# FPGA.net
KiCad netlist of a schematic drawn in Altium Designer
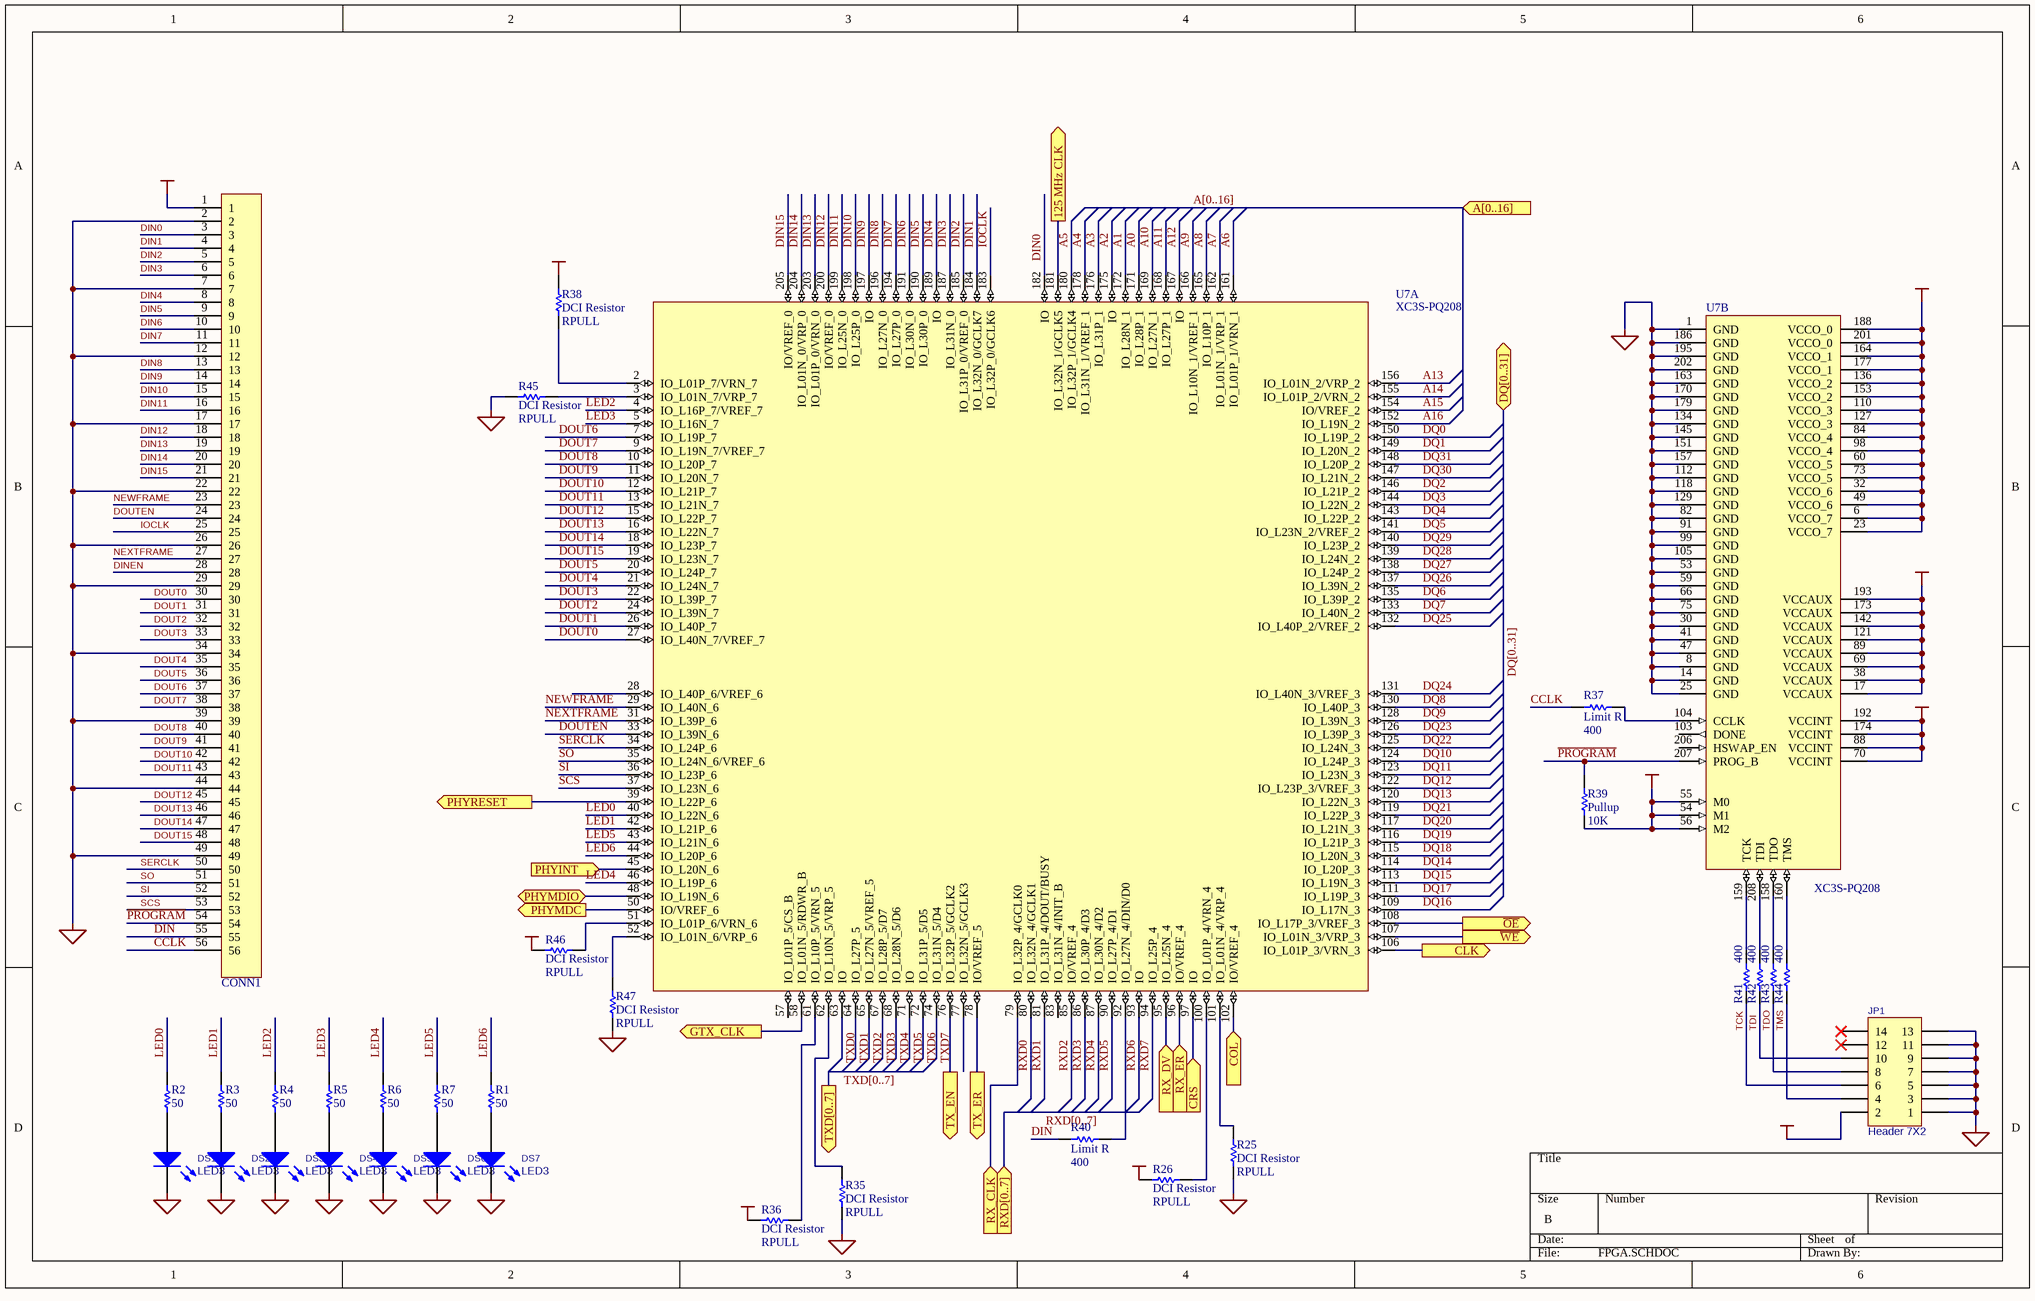
[diagram p0: FPGA.SCHDOC]

(export (version "E")
  (design (tool "Eeschema 10.0.6"))
  (components
    (comp (ref "CONN1") (value "CON56B") (footprint "HDR56F") (libsource (lib "parts") (part "CON56B")))
    (comp (ref "DS1")
      (value "LED3")
      (footprint "SMD _LED")
      (description "Typical BLUE SiC LED")
      (fields (field (name "PUBLISHER") "Altium Limited"))
      (libsource (lib "Miscellaneous Devices") (part "LED3"))
    )
    (comp (ref "DS2")
      (value "LED3")
      (footprint "SMD _LED")
      (description "Typical BLUE SiC LED")
      (fields (field (name "PUBLISHER") "Altium Limited"))
      (libsource (lib "Miscellaneous Devices") (part "LED3"))
    )
    (comp (ref "DS3")
      (value "LED3")
      (footprint "SMD _LED")
      (description "Typical BLUE SiC LED")
      (fields (field (name "PUBLISHER") "Altium Limited"))
      (libsource (lib "Miscellaneous Devices") (part "LED3"))
    )
    (comp (ref "DS4")
      (value "LED3")
      (footprint "SMD _LED")
      (description "Typical BLUE SiC LED")
      (fields (field (name "PUBLISHER") "Altium Limited"))
      (libsource (lib "Miscellaneous Devices") (part "LED3"))
    )
    (comp (ref "DS5")
      (value "LED3")
      (footprint "SMD _LED")
      (description "Typical BLUE SiC LED")
      (fields (field (name "PUBLISHER") "Altium Limited"))
      (libsource (lib "Miscellaneous Devices") (part "LED3"))
    )
    (comp (ref "DS6")
      (value "LED3")
      (footprint "SMD _LED")
      (description "Typical BLUE SiC LED")
      (fields (field (name "PUBLISHER") "Altium Limited"))
      (libsource (lib "Miscellaneous Devices") (part "LED3"))
    )
    (comp (ref "DS7")
      (value "LED3")
      (footprint "SMD _LED")
      (description "Typical BLUE SiC LED")
      (fields (field (name "PUBLISHER") "Altium Limited"))
      (libsource (lib "Miscellaneous Devices") (part "LED3"))
    )
    (comp (ref "JP1")
      (value "Header 7X2")
      (footprint "SMT 2x7 2mm HDR")
      (description "Header, 7-Pin, Dual row")
      (fields (field (name "MANUFACTURER") "Generic Components") (field (name "PUBLISHER") "Altium Limited"))
      (libsource (lib "Miscellaneous Connectors") (part "Header 7X2"))
    )
    (comp (ref "R1")
      (value "50")
      (footprint "0603")
      (description "Standard Passive Resistor")
      (fields (field (name "TOLERANCE") "1%") (field (name "Comment") "RESISTOR"))
      (libsource (lib "parts") (part "RESISTOR"))
    )
    (comp (ref "R2")
      (value "50")
      (footprint "0603")
      (description "Standard Passive Resistor")
      (fields (field (name "TOLERANCE") "1%") (field (name "Comment") "RESISTOR"))
      (libsource (lib "parts") (part "RESISTOR"))
    )
    (comp (ref "R3")
      (value "50")
      (footprint "0603")
      (description "Standard Passive Resistor")
      (fields (field (name "TOLERANCE") "1%") (field (name "Comment") "RESISTOR"))
      (libsource (lib "parts") (part "RESISTOR"))
    )
    (comp (ref "R4")
      (value "50")
      (footprint "0603")
      (description "Standard Passive Resistor")
      (fields (field (name "TOLERANCE") "1%") (field (name "Comment") "RESISTOR"))
      (libsource (lib "parts") (part "RESISTOR"))
    )
    (comp (ref "R5")
      (value "50")
      (footprint "0603")
      (description "Standard Passive Resistor")
      (fields (field (name "TOLERANCE") "1%") (field (name "Comment") "RESISTOR"))
      (libsource (lib "parts") (part "RESISTOR"))
    )
    (comp (ref "R6")
      (value "50")
      (footprint "0603")
      (description "Standard Passive Resistor")
      (fields (field (name "TOLERANCE") "1%") (field (name "Comment") "RESISTOR"))
      (libsource (lib "parts") (part "RESISTOR"))
    )
    (comp (ref "R7")
      (value "50")
      (footprint "0603")
      (description "Standard Passive Resistor")
      (fields (field (name "TOLERANCE") "1%") (field (name "Comment") "RESISTOR"))
      (libsource (lib "parts") (part "RESISTOR"))
    )
    (comp (ref "R25")
      (value "DCI Resistor")
      (footprint "0603")
      (description "Resistor")
      (fields
        (field (name "MANUFACTURER") "Generic Components")
        (field (name "ALTIUM_VALUE") "RPULL")
        (field (name "PUBLISHER") "Altium Limited")
      )
      (libsource (lib "Miscellaneous Devices") (part "Res1"))
    )
    (comp (ref "R26")
      (value "DCI Resistor")
      (footprint "0603")
      (description "Resistor")
      (fields
        (field (name "MANUFACTURER") "Generic Components")
        (field (name "ALTIUM_VALUE") "RPULL")
        (field (name "PUBLISHER") "Altium Limited")
      )
      (libsource (lib "Miscellaneous Devices") (part "Res1"))
    )
    (comp (ref "R35")
      (value "DCI Resistor")
      (footprint "0603")
      (description "Resistor")
      (fields
        (field (name "MANUFACTURER") "Generic Components")
        (field (name "ALTIUM_VALUE") "RPULL")
        (field (name "PUBLISHER") "Altium Limited")
      )
      (libsource (lib "Miscellaneous Devices") (part "Res1"))
    )
    (comp (ref "R36")
      (value "DCI Resistor")
      (footprint "0603")
      (description "Resistor")
      (fields
        (field (name "MANUFACTURER") "Generic Components")
        (field (name "ALTIUM_VALUE") "RPULL")
        (field (name "PUBLISHER") "Altium Limited")
      )
      (libsource (lib "Miscellaneous Devices") (part "Res1"))
    )
    (comp (ref "R37")
      (value "Limit R")
      (footprint "0603")
      (description "Standard Passive Resistor")
      (fields (field (name "ALTIUM_VALUE") "400") (field (name "TOLERANCE") "1%"))
      (libsource (lib "parts") (part "RESISTOR"))
    )
    (comp (ref "R38")
      (value "DCI Resistor")
      (footprint "0603")
      (description "Resistor")
      (fields
        (field (name "MANUFACTURER") "Generic Components")
        (field (name "ALTIUM_VALUE") "RPULL")
        (field (name "PUBLISHER") "Altium Limited")
      )
      (libsource (lib "Miscellaneous Devices") (part "Res1"))
    )
    (comp (ref "R39")
      (value "Pullup")
      (footprint "0603")
      (description "Resistor")
      (fields
        (field (name "MANUFACTURER") "Generic Components")
        (field (name "ALTIUM_VALUE") "10K")
        (field (name "PUBLISHER") "Altium Limited")
      )
      (libsource (lib "Miscellaneous Devices") (part "Res1"))
    )
    (comp (ref "R40")
      (value "Limit R")
      (footprint "0603")
      (description "Standard Passive Resistor")
      (fields (field (name "ALTIUM_VALUE") "400") (field (name "TOLERANCE") "1%"))
      (libsource (lib "parts") (part "RESISTOR"))
    )
    (comp (ref "R41")
      (value "400")
      (footprint "0603")
      (description "Standard Passive Resistor")
      (fields (field (name "TOLERANCE") "1%") (field (name "Comment") "RESISTOR"))
      (libsource (lib "parts") (part "RESISTOR"))
    )
    (comp (ref "R42")
      (value "400")
      (footprint "0603")
      (description "Standard Passive Resistor")
      (fields (field (name "TOLERANCE") "1%") (field (name "Comment") "RESISTOR"))
      (libsource (lib "parts") (part "RESISTOR"))
    )
    (comp (ref "R43")
      (value "400")
      (footprint "0603")
      (description "Standard Passive Resistor")
      (fields (field (name "TOLERANCE") "1%") (field (name "Comment") "RESISTOR"))
      (libsource (lib "parts") (part "RESISTOR"))
    )
    (comp (ref "R44")
      (value "400")
      (footprint "0603")
      (description "Standard Passive Resistor")
      (fields (field (name "TOLERANCE") "1%") (field (name "Comment") "RESISTOR"))
      (libsource (lib "parts") (part "RESISTOR"))
    )
    (comp (ref "R45")
      (value "DCI Resistor")
      (footprint "0603")
      (description "Resistor")
      (fields
        (field (name "MANUFACTURER") "Generic Components")
        (field (name "ALTIUM_VALUE") "RPULL")
        (field (name "PUBLISHER") "Altium Limited")
      )
      (libsource (lib "Miscellaneous Devices") (part "Res1"))
    )
    (comp (ref "R46")
      (value "DCI Resistor")
      (footprint "0603")
      (description "Resistor")
      (fields
        (field (name "MANUFACTURER") "Generic Components")
        (field (name "ALTIUM_VALUE") "RPULL")
        (field (name "PUBLISHER") "Altium Limited")
      )
      (libsource (lib "Miscellaneous Devices") (part "Res1"))
    )
    (comp (ref "R47")
      (value "DCI Resistor")
      (footprint "0603")
      (description "Resistor")
      (fields
        (field (name "MANUFACTURER") "Generic Components")
        (field (name "ALTIUM_VALUE") "RPULL")
        (field (name "PUBLISHER") "Altium Limited")
      )
      (libsource (lib "Miscellaneous Devices") (part "Res1"))
    )
    (comp (ref "U7")
      (value "XC3S-PQ208")
      (footprint "F-QFP28X28-G208/Z32N")
      (description "Xilinx Spartan-3 PQ208")
      (libsource (lib "My devices") (part "XC3S-PQ208"))
    )
  )
  (nets
    (net (code "1") (name "+1.2VCC") (class "Default")
      (node (ref "U7") (pin "174") (pinfunction "VCCINT_174") (pintype "power_in"))
      (node (ref "U7") (pin "192") (pinfunction "VCCINT_192") (pintype "power_in"))
      (node (ref "U7") (pin "70") (pinfunction "VCCINT_70") (pintype "power_in"))
      (node (ref "U7") (pin "88") (pinfunction "VCCINT_88") (pintype "power_in"))
    )
    (net (code "2") (name "+2.5VCC") (class "Default")
      (node (ref "U7") (pin "121") (pinfunction "VCCAUX_121") (pintype "power_in"))
      (node (ref "U7") (pin "142") (pinfunction "VCCAUX_142") (pintype "power_in"))
      (node (ref "U7") (pin "17") (pinfunction "VCCAUX_17") (pintype "power_in"))
      (node (ref "U7") (pin "173") (pinfunction "VCCAUX_173") (pintype "power_in"))
      (node (ref "U7") (pin "193") (pinfunction "VCCAUX_193") (pintype "power_in"))
      (node (ref "U7") (pin "38") (pinfunction "VCCAUX_38") (pintype "power_in"))
      (node (ref "U7") (pin "69") (pinfunction "VCCAUX_69") (pintype "power_in"))
      (node (ref "U7") (pin "89") (pinfunction "VCCAUX_89") (pintype "power_in"))
    )
    (net (code "3") (name "/125 MHz CLK") (class "Default")
      (node (ref "U7") (pin "181") (pinfunction "IO_L32N_1/GCLK5_181") (pintype "bidirectional"))
    )
    (net (code "4") (name "/A0") (class "Default")
      (node (ref "U7") (pin "171") (pinfunction "IO_L28P_1_171") (pintype "bidirectional"))
    )
    (net (code "5") (name "/A1") (class "Default")
      (node (ref "U7") (pin "172") (pinfunction "IO_L28N_1_172") (pintype "bidirectional"))
    )
    (net (code "6") (name "/A2") (class "Default")
      (node (ref "U7") (pin "175") (pinfunction "IO_175") (pintype "bidirectional"))
    )
    (net (code "7") (name "/A3") (class "Default")
      (node (ref "U7") (pin "176") (pinfunction "IO_L31P_1_176") (pintype "bidirectional"))
    )
    (net (code "8") (name "/A4") (class "Default")
      (node (ref "U7") (pin "178") (pinfunction "IO_L31N_1/VREF_1_178") (pintype "bidirectional"))
    )
    (net (code "9") (name "/A5") (class "Default")
      (node (ref "U7") (pin "180") (pinfunction "IO_L32P_1/GCLK4_180") (pintype "bidirectional"))
    )
    (net (code "10") (name "/A6") (class "Default")
      (node (ref "U7") (pin "161") (pinfunction "IO_L01P_1/VRN_1_161") (pintype "bidirectional"))
    )
    (net (code "11") (name "/A7") (class "Default")
      (node (ref "U7") (pin "162") (pinfunction "IO_L01N_1/VRP_1_162") (pintype "bidirectional"))
    )
    (net (code "12") (name "/A8") (class "Default")
      (node (ref "U7") (pin "165") (pinfunction "IO_L10P_1_165") (pintype "bidirectional"))
    )
    (net (code "13") (name "/A9") (class "Default")
      (node (ref "U7") (pin "166") (pinfunction "IO_L10N_1/VREF_1_166") (pintype "bidirectional"))
    )
    (net (code "14") (name "/A10") (class "Default")
      (node (ref "U7") (pin "169") (pinfunction "IO_L27N_1_169") (pintype "bidirectional"))
    )
    (net (code "15") (name "/A11") (class "Default")
      (node (ref "U7") (pin "168") (pinfunction "IO_L27P_1_168") (pintype "bidirectional"))
    )
    (net (code "16") (name "/A12") (class "Default")
      (node (ref "U7") (pin "167") (pinfunction "IO_167") (pintype "bidirectional"))
    )
    (net (code "17") (name "/A13") (class "Default")
      (node (ref "U7") (pin "156") (pinfunction "IO_L01N_2/VRP_2_156") (pintype "bidirectional"))
    )
    (net (code "18") (name "/A14") (class "Default")
      (node (ref "U7") (pin "155") (pinfunction "IO_L01P_2/VRN_2_155") (pintype "bidirectional"))
    )
    (net (code "19") (name "/A15") (class "Default")
      (node (ref "U7") (pin "154") (pinfunction "IO/VREF_2_154") (pintype "bidirectional"))
    )
    (net (code "20") (name "/A16") (class "Default")
      (node (ref "U7") (pin "152") (pinfunction "IO_L19N_2_152") (pintype "bidirectional"))
    )
    (net (code "22") (name "/CCLK") (class "Default")
      (node (ref "CONN1") (pin "56") (pinfunction "56_56") (pintype "passive"))
      (node (ref "R37") (pin "2") (pintype "passive"))
    )
    (net (code "23") (name "/CLK") (class "Default")
      (node (ref "U7") (pin "106") (pinfunction "IO_L01P_3/VRN_3_106") (pintype "bidirectional"))
    )
    (net (code "24") (name "/COL") (class "Default")
      (node (ref "U7") (pin "102") (pinfunction "IO/VREF_4_102") (pintype "bidirectional"))
    )
    (net (code "25") (name "/CRS") (class "Default")
      (node (ref "U7") (pin "97") (pinfunction "IO_97") (pintype "bidirectional"))
    )
    (net (code "26") (name "/DIN") (class "Default")
      (node (ref "CONN1") (pin "55") (pinfunction "55_55") (pintype "passive"))
      (node (ref "R40") (pin "2") (pintype "passive"))
    )
    (net (code "27") (name "/DIN0") (class "Default")
      (node (ref "CONN1") (pin "3") (pinfunction "3_3") (pintype "passive"))
      (node (ref "U7") (pin "182") (pinfunction "IO_182") (pintype "bidirectional"))
    )
    (net (code "28") (name "/DIN1") (class "Default")
      (node (ref "CONN1") (pin "4") (pinfunction "4_4") (pintype "passive"))
      (node (ref "U7") (pin "184") (pinfunction "IO_L32N_0/GCLK7_184") (pintype "bidirectional"))
    )
    (net (code "29") (name "/DIN2") (class "Default")
      (node (ref "CONN1") (pin "5") (pinfunction "5_5") (pintype "passive"))
      (node (ref "U7") (pin "185") (pinfunction "IO_L31P_0/VREF_0_185") (pintype "bidirectional"))
    )
    (net (code "30") (name "/DIN3") (class "Default")
      (node (ref "CONN1") (pin "6") (pinfunction "6_6") (pintype "passive"))
      (node (ref "U7") (pin "187") (pinfunction "IO_L31N_0_187") (pintype "bidirectional"))
    )
    (net (code "31") (name "/DIN4") (class "Default")
      (node (ref "CONN1") (pin "8") (pinfunction "8_8") (pintype "passive"))
      (node (ref "U7") (pin "189") (pinfunction "IO_189") (pintype "bidirectional"))
    )
    (net (code "32") (name "/DIN5") (class "Default")
      (node (ref "CONN1") (pin "9") (pinfunction "9_9") (pintype "passive"))
      (node (ref "U7") (pin "190") (pinfunction "IO_L30P_0_190") (pintype "bidirectional"))
    )
    (net (code "33") (name "/DIN6") (class "Default")
      (node (ref "CONN1") (pin "10") (pinfunction "10_10") (pintype "passive"))
      (node (ref "U7") (pin "191") (pinfunction "IO_L30N_0_191") (pintype "bidirectional"))
    )
    (net (code "34") (name "/DIN7") (class "Default")
      (node (ref "CONN1") (pin "11") (pinfunction "11_11") (pintype "passive"))
      (node (ref "U7") (pin "194") (pinfunction "IO_L27P_0_194") (pintype "bidirectional"))
    )
    (net (code "35") (name "/DIN8") (class "Default")
      (node (ref "CONN1") (pin "13") (pinfunction "13_13") (pintype "passive"))
      (node (ref "U7") (pin "196") (pinfunction "IO_L27N_0_196") (pintype "bidirectional"))
    )
    (net (code "36") (name "/DIN9") (class "Default")
      (node (ref "CONN1") (pin "14") (pinfunction "14_14") (pintype "passive"))
      (node (ref "U7") (pin "197") (pinfunction "IO_197") (pintype "bidirectional"))
    )
    (net (code "37") (name "/DIN10") (class "Default")
      (node (ref "CONN1") (pin "15") (pinfunction "15_15") (pintype "passive"))
      (node (ref "U7") (pin "198") (pinfunction "IO_L25P_0_198") (pintype "bidirectional"))
    )
    (net (code "38") (name "/DIN11") (class "Default")
      (node (ref "CONN1") (pin "16") (pinfunction "16_16") (pintype "passive"))
      (node (ref "U7") (pin "199") (pinfunction "IO_L25N_0_199") (pintype "bidirectional"))
    )
    (net (code "39") (name "/DIN12") (class "Default")
      (node (ref "CONN1") (pin "18") (pinfunction "18_18") (pintype "passive"))
      (node (ref "U7") (pin "200") (pinfunction "IO/VREF_0_200") (pintype "bidirectional"))
    )
    (net (code "40") (name "/DIN13") (class "Default")
      (node (ref "CONN1") (pin "19") (pinfunction "19_19") (pintype "passive"))
      (node (ref "U7") (pin "203") (pinfunction "IO_L01P_0/VRN_0_203") (pintype "bidirectional"))
    )
    (net (code "41") (name "/DIN14") (class "Default")
      (node (ref "CONN1") (pin "20") (pinfunction "20_20") (pintype "passive"))
      (node (ref "U7") (pin "204") (pinfunction "IO_L01N_0/VRP_0_204") (pintype "bidirectional"))
    )
    (net (code "42") (name "/DIN15") (class "Default")
      (node (ref "CONN1") (pin "21") (pinfunction "21_21") (pintype "passive"))
      (node (ref "U7") (pin "205") (pinfunction "IO/VREF_0_205") (pintype "bidirectional"))
    )
    (net (code "43") (name "/DINEN") (class "Default")
      (node (ref "CONN1") (pin "28") (pinfunction "28_28") (pintype "passive"))
    )
    (net (code "44") (name "/DOUT0") (class "Default")
      (node (ref "CONN1") (pin "30") (pinfunction "30_30") (pintype "passive"))
      (node (ref "U7") (pin "27") (pinfunction "IO_L40N_7/VREF_7_27") (pintype "bidirectional"))
    )
    (net (code "45") (name "/DOUT1") (class "Default")
      (node (ref "CONN1") (pin "31") (pinfunction "31_31") (pintype "passive"))
      (node (ref "U7") (pin "26") (pinfunction "IO_L40P_7_26") (pintype "bidirectional"))
    )
    (net (code "46") (name "/DOUT2") (class "Default")
      (node (ref "CONN1") (pin "32") (pinfunction "32_32") (pintype "passive"))
      (node (ref "U7") (pin "24") (pinfunction "IO_L39N_7_24") (pintype "bidirectional"))
    )
    (net (code "47") (name "/DOUT3") (class "Default")
      (node (ref "CONN1") (pin "33") (pinfunction "33_33") (pintype "passive"))
      (node (ref "U7") (pin "22") (pinfunction "IO_L39P_7_22") (pintype "bidirectional"))
    )
    (net (code "48") (name "/DOUT4") (class "Default")
      (node (ref "CONN1") (pin "35") (pinfunction "35_35") (pintype "passive"))
      (node (ref "U7") (pin "21") (pinfunction "IO_L24N_7_21") (pintype "bidirectional"))
    )
    (net (code "49") (name "/DOUT5") (class "Default")
      (node (ref "CONN1") (pin "36") (pinfunction "36_36") (pintype "passive"))
      (node (ref "U7") (pin "20") (pinfunction "IO_L24P_7_20") (pintype "bidirectional"))
    )
    (net (code "50") (name "/DOUT6") (class "Default")
      (node (ref "CONN1") (pin "37") (pinfunction "37_37") (pintype "passive"))
      (node (ref "U7") (pin "7") (pinfunction "IO_L19P_7_7") (pintype "bidirectional"))
    )
    (net (code "51") (name "/DOUT7") (class "Default")
      (node (ref "CONN1") (pin "38") (pinfunction "38_38") (pintype "passive"))
      (node (ref "U7") (pin "9") (pinfunction "IO_L19N_7/VREF_7_9") (pintype "bidirectional"))
    )
    (net (code "52") (name "/DOUT8") (class "Default")
      (node (ref "CONN1") (pin "40") (pinfunction "40_40") (pintype "passive"))
      (node (ref "U7") (pin "10") (pinfunction "IO_L20P_7_10") (pintype "bidirectional"))
    )
    (net (code "53") (name "/DOUT9") (class "Default")
      (node (ref "CONN1") (pin "41") (pinfunction "41_41") (pintype "passive"))
      (node (ref "U7") (pin "11") (pinfunction "IO_L20N_7_11") (pintype "bidirectional"))
    )
    (net (code "54") (name "/DOUT10") (class "Default")
      (node (ref "CONN1") (pin "42") (pinfunction "42_42") (pintype "passive"))
      (node (ref "U7") (pin "12") (pinfunction "IO_L21P_7_12") (pintype "bidirectional"))
    )
    (net (code "55") (name "/DOUT11") (class "Default")
      (node (ref "CONN1") (pin "43") (pinfunction "43_43") (pintype "passive"))
      (node (ref "U7") (pin "13") (pinfunction "IO_L21N_7_13") (pintype "bidirectional"))
    )
    (net (code "56") (name "/DOUT12") (class "Default")
      (node (ref "CONN1") (pin "45") (pinfunction "45_45") (pintype "passive"))
      (node (ref "U7") (pin "15") (pinfunction "IO_L22P_7_15") (pintype "bidirectional"))
    )
    (net (code "57") (name "/DOUT13") (class "Default")
      (node (ref "CONN1") (pin "46") (pinfunction "46_46") (pintype "passive"))
      (node (ref "U7") (pin "16") (pinfunction "IO_L22N_7_16") (pintype "bidirectional"))
    )
    (net (code "58") (name "/DOUT14") (class "Default")
      (node (ref "CONN1") (pin "47") (pinfunction "47_47") (pintype "passive"))
      (node (ref "U7") (pin "18") (pinfunction "IO_L23P_7_18") (pintype "bidirectional"))
    )
    (net (code "59") (name "/DOUT15") (class "Default")
      (node (ref "CONN1") (pin "48") (pinfunction "48_48") (pintype "passive"))
      (node (ref "U7") (pin "19") (pinfunction "IO_L23N_7_19") (pintype "bidirectional"))
    )
    (net (code "60") (name "/DOUTEN") (class "Default")
      (node (ref "CONN1") (pin "24") (pinfunction "24_24") (pintype "passive"))
      (node (ref "U7") (pin "33") (pinfunction "IO_L39N_6_33") (pintype "bidirectional"))
    )
    (net (code "61") (name "/DQ0") (class "Default")
      (node (ref "U7") (pin "150") (pinfunction "IO_L19P_2_150") (pintype "bidirectional"))
    )
    (net (code "62") (name "/DQ1") (class "Default")
      (node (ref "U7") (pin "149") (pinfunction "IO_L20N_2_149") (pintype "bidirectional"))
    )
    (net (code "63") (name "/DQ2") (class "Default")
      (node (ref "U7") (pin "146") (pinfunction "IO_L21P_2_146") (pintype "bidirectional"))
    )
    (net (code "64") (name "/DQ3") (class "Default")
      (node (ref "U7") (pin "144") (pinfunction "IO_L22N_2_144") (pintype "bidirectional"))
    )
    (net (code "65") (name "/DQ4") (class "Default")
      (node (ref "U7") (pin "143") (pinfunction "IO_L22P_2_143") (pintype "bidirectional"))
    )
    (net (code "66") (name "/DQ5") (class "Default")
      (node (ref "U7") (pin "141") (pinfunction "IO_L23N_2/VREF_2_141") (pintype "bidirectional"))
    )
    (net (code "67") (name "/DQ6") (class "Default")
      (node (ref "U7") (pin "135") (pinfunction "IO_L39P_2_135") (pintype "bidirectional"))
    )
    (net (code "68") (name "/DQ7") (class "Default")
      (node (ref "U7") (pin "133") (pinfunction "IO_L40N_2_133") (pintype "bidirectional"))
    )
    (net (code "69") (name "/DQ8") (class "Default")
      (node (ref "U7") (pin "130") (pinfunction "IO_L40P_3_130") (pintype "bidirectional"))
    )
    (net (code "70") (name "/DQ9") (class "Default")
      (node (ref "U7") (pin "128") (pinfunction "IO_L39N_3_128") (pintype "bidirectional"))
    )
    (net (code "71") (name "/DQ10") (class "Default")
      (node (ref "U7") (pin "124") (pinfunction "IO_L24P_3_124") (pintype "bidirectional"))
    )
    (net (code "72") (name "/DQ11") (class "Default")
      (node (ref "U7") (pin "123") (pinfunction "IO_L23N_3_123") (pintype "bidirectional"))
    )
    (net (code "73") (name "/DQ12") (class "Default")
      (node (ref "U7") (pin "122") (pinfunction "IO_L23P_3/VREF_3_122") (pintype "bidirectional"))
    )
    (net (code "74") (name "/DQ13") (class "Default")
      (node (ref "U7") (pin "120") (pinfunction "IO_L22N_3_120") (pintype "bidirectional"))
    )
    (net (code "75") (name "/DQ14") (class "Default")
      (node (ref "U7") (pin "114") (pinfunction "IO_L20P_3_114") (pintype "bidirectional"))
    )
    (net (code "76") (name "/DQ15") (class "Default")
      (node (ref "U7") (pin "113") (pinfunction "IO_L19N_3_113") (pintype "bidirectional"))
    )
    (net (code "77") (name "/DQ16") (class "Default")
      (node (ref "U7") (pin "109") (pinfunction "IO_L17N_3_109") (pintype "bidirectional"))
    )
    (net (code "78") (name "/DQ17") (class "Default")
      (node (ref "U7") (pin "111") (pinfunction "IO_L19P_3_111") (pintype "bidirectional"))
    )
    (net (code "79") (name "/DQ18") (class "Default")
      (node (ref "U7") (pin "115") (pinfunction "IO_L20N_3_115") (pintype "bidirectional"))
    )
    (net (code "80") (name "/DQ19") (class "Default")
      (node (ref "U7") (pin "116") (pinfunction "IO_L21P_3_116") (pintype "bidirectional"))
    )
    (net (code "81") (name "/DQ20") (class "Default")
      (node (ref "U7") (pin "117") (pinfunction "IO_L21N_3_117") (pintype "bidirectional"))
    )
    (net (code "82") (name "/DQ21") (class "Default")
      (node (ref "U7") (pin "119") (pinfunction "IO_L22P_3_119") (pintype "bidirectional"))
    )
    (net (code "83") (name "/DQ22") (class "Default")
      (node (ref "U7") (pin "125") (pinfunction "IO_L24N_3_125") (pintype "bidirectional"))
    )
    (net (code "84") (name "/DQ23") (class "Default")
      (node (ref "U7") (pin "126") (pinfunction "IO_L39P_3_126") (pintype "bidirectional"))
    )
    (net (code "85") (name "/DQ24") (class "Default")
      (node (ref "U7") (pin "131") (pinfunction "IO_L40N_3/VREF_3_131") (pintype "bidirectional"))
    )
    (net (code "86") (name "/DQ25") (class "Default")
      (node (ref "U7") (pin "132") (pinfunction "IO_L40P_2/VREF_2_132") (pintype "bidirectional"))
    )
    (net (code "87") (name "/DQ26") (class "Default")
      (node (ref "U7") (pin "137") (pinfunction "IO_L39N_2_137") (pintype "bidirectional"))
    )
    (net (code "88") (name "/DQ27") (class "Default")
      (node (ref "U7") (pin "138") (pinfunction "IO_L24P_2_138") (pintype "bidirectional"))
    )
    (net (code "89") (name "/DQ28") (class "Default")
      (node (ref "U7") (pin "139") (pinfunction "IO_L24N_2_139") (pintype "bidirectional"))
    )
    (net (code "90") (name "/DQ29") (class "Default")
      (node (ref "U7") (pin "140") (pinfunction "IO_L23P_2_140") (pintype "bidirectional"))
    )
    (net (code "91") (name "/DQ30") (class "Default")
      (node (ref "U7") (pin "147") (pinfunction "IO_L21N_2_147") (pintype "bidirectional"))
    )
    (net (code "92") (name "/DQ31") (class "Default")
      (node (ref "U7") (pin "148") (pinfunction "IO_L20P_2_148") (pintype "bidirectional"))
    )
    (net (code "94") (name "/GTX_CLK") (class "Default")
      (node (ref "U7") (pin "58") (pinfunction "IO_L01N_5/RDWR_B_58") (pintype "bidirectional"))
    )
    (net (code "95") (name "/IOCLK") (class "Default")
      (node (ref "CONN1") (pin "25") (pinfunction "25_25") (pintype "passive"))
      (node (ref "U7") (pin "183") (pinfunction "IO_L32P_0/GCLK6_183") (pintype "bidirectional"))
    )
    (net (code "96") (name "/LED0") (class "Default")
      (node (ref "R2") (pin "2") (pintype "passive"))
      (node (ref "U7") (pin "40") (pinfunction "IO_L22N_6_40") (pintype "bidirectional"))
    )
    (net (code "97") (name "/LED1") (class "Default")
      (node (ref "R3") (pin "2") (pintype "passive"))
      (node (ref "U7") (pin "42") (pinfunction "IO_L21P_6_42") (pintype "bidirectional"))
    )
    (net (code "98") (name "/LED2") (class "Default")
      (node (ref "R4") (pin "2") (pintype "passive"))
      (node (ref "U7") (pin "4") (pinfunction "IO_L16P_7/VREF_7_4") (pintype "bidirectional"))
    )
    (net (code "99") (name "/LED3") (class "Default")
      (node (ref "R5") (pin "2") (pintype "passive"))
      (node (ref "U7") (pin "5") (pinfunction "IO_L16N_7_5") (pintype "bidirectional"))
    )
    (net (code "100") (name "/LED4") (class "Default")
      (node (ref "R6") (pin "2") (pintype "passive"))
      (node (ref "U7") (pin "46") (pinfunction "IO_L19P_6_46") (pintype "bidirectional"))
    )
    (net (code "101") (name "/LED5") (class "Default")
      (node (ref "R7") (pin "2") (pintype "passive"))
      (node (ref "U7") (pin "43") (pinfunction "IO_L21N_6_43") (pintype "bidirectional"))
    )
    (net (code "102") (name "/LED6") (class "Default")
      (node (ref "R1") (pin "2") (pintype "passive"))
      (node (ref "U7") (pin "44") (pinfunction "IO_L20P_6_44") (pintype "bidirectional"))
    )
    (net (code "103") (name "/NEWFRAME") (class "Default")
      (node (ref "CONN1") (pin "23") (pinfunction "23_23") (pintype "passive"))
      (node (ref "U7") (pin "29") (pinfunction "IO_L40N_6_29") (pintype "bidirectional"))
    )
    (net (code "104") (name "/NEXTFRAME") (class "Default")
      (node (ref "CONN1") (pin "27") (pinfunction "27_27") (pintype "passive"))
      (node (ref "U7") (pin "31") (pinfunction "IO_L39P_6_31") (pintype "bidirectional"))
    )
    (net (code "105") (name "/PHYINT") (class "Default")
      (node (ref "U7") (pin "45") (pinfunction "IO_L20N_6_45") (pintype "bidirectional"))
    )
    (net (code "106") (name "/PHYMDC") (class "Default")
      (node (ref "U7") (pin "50") (pinfunction "IO/VREF_6_50") (pintype "bidirectional"))
    )
    (net (code "107") (name "/PHYMDIO") (class "Default")
      (node (ref "U7") (pin "48") (pinfunction "IO_L19N_6_48") (pintype "bidirectional"))
    )
    (net (code "108") (name "/PHYRESET") (class "Default")
      (node (ref "U7") (pin "39") (pinfunction "IO_L22P_6_39") (pintype "bidirectional"))
    )
    (net (code "109") (name "/RXD0") (class "Default")
      (node (ref "U7") (pin "80") (pinfunction "IO_L32N_4/GCLK1_80") (pintype "bidirectional"))
    )
    (net (code "110") (name "/RXD1") (class "Default")
      (node (ref "U7") (pin "81") (pinfunction "IO_L31P_4/DOUT/BUSY_81") (pintype "bidirectional"))
    )
    (net (code "111") (name "/RXD2") (class "Default")
      (node (ref "U7") (pin "85") (pinfunction "IO/VREF_4_85") (pintype "bidirectional"))
    )
    (net (code "112") (name "/RXD3") (class "Default")
      (node (ref "U7") (pin "86") (pinfunction "IO_L30P_4/D3_86") (pintype "bidirectional"))
    )
    (net (code "113") (name "/RXD4") (class "Default")
      (node (ref "U7") (pin "87") (pinfunction "IO_L30N_4/D2_87") (pintype "bidirectional"))
    )
    (net (code "114") (name "/RXD5") (class "Default")
      (node (ref "U7") (pin "90") (pinfunction "IO_L27P_4/D1_90") (pintype "bidirectional"))
    )
    (net (code "115") (name "/RXD6") (class "Default")
      (node (ref "U7") (pin "93") (pinfunction "IO_93") (pintype "bidirectional"))
    )
    (net (code "116") (name "/RXD7") (class "Default")
      (node (ref "U7") (pin "94") (pinfunction "IO_L25P_4_94") (pintype "bidirectional"))
    )
    (net (code "118") (name "/RX_CLK") (class "Default")
      (node (ref "U7") (pin "79") (pinfunction "IO_L32P_4/GCLK0_79") (pintype "bidirectional"))
    )
    (net (code "119") (name "/RX_DV") (class "Default")
      (node (ref "U7") (pin "95") (pinfunction "IO_L25N_4_95") (pintype "bidirectional"))
    )
    (net (code "120") (name "/RX_ER") (class "Default")
      (node (ref "U7") (pin "96") (pinfunction "IO/VREF_4_96") (pintype "bidirectional"))
    )
    (net (code "121") (name "/SCS") (class "Default")
      (node (ref "CONN1") (pin "53") (pinfunction "53_53") (pintype "passive"))
      (node (ref "U7") (pin "37") (pinfunction "IO_L23N_6_37") (pintype "bidirectional"))
    )
    (net (code "122") (name "/SERCLK") (class "Default")
      (node (ref "CONN1") (pin "50") (pinfunction "50_50") (pintype "passive"))
      (node (ref "U7") (pin "34") (pinfunction "IO_L24P_6_34") (pintype "bidirectional"))
    )
    (net (code "123") (name "/SI") (class "Default")
      (node (ref "CONN1") (pin "52") (pinfunction "52_52") (pintype "passive"))
      (node (ref "U7") (pin "36") (pinfunction "IO_L23P_6_36") (pintype "bidirectional"))
    )
    (net (code "124") (name "/SO") (class "Default")
      (node (ref "CONN1") (pin "51") (pinfunction "51_51") (pintype "passive"))
      (node (ref "U7") (pin "35") (pinfunction "IO_L24N_6/VREF_6_35") (pintype "bidirectional"))
    )
    (net (code "125") (name "/TCK") (class "Default")
      (node (ref "JP1") (pin "6") (pinfunction "6_6") (pintype "passive"))
      (node (ref "R41") (pin "2") (pintype "passive"))
    )
    (net (code "126") (name "/TDI") (class "Default")
      (node (ref "JP1") (pin "10") (pinfunction "10_10") (pintype "passive"))
      (node (ref "R42") (pin "2") (pintype "passive"))
    )
    (net (code "127") (name "/TDO") (class "Default")
      (node (ref "JP1") (pin "8") (pinfunction "8_8") (pintype "passive"))
      (node (ref "R43") (pin "2") (pintype "passive"))
    )
    (net (code "128") (name "/TMS") (class "Default")
      (node (ref "JP1") (pin "4") (pinfunction "4_4") (pintype "passive"))
      (node (ref "R44") (pin "2") (pintype "passive"))
    )
    (net (code "129") (name "/TXD0") (class "Default")
      (node (ref "U7") (pin "63") (pinfunction "IO_63") (pintype "bidirectional"))
    )
    (net (code "130") (name "/TXD1") (class "Default")
      (node (ref "U7") (pin "64") (pinfunction "IO_L27P_5_64") (pintype "bidirectional"))
    )
    (net (code "131") (name "/TXD2") (class "Default")
      (node (ref "U7") (pin "65") (pinfunction "IO_L27N_5/VREF_5_65") (pintype "bidirectional"))
    )
    (net (code "132") (name "/TXD3") (class "Default")
      (node (ref "U7") (pin "67") (pinfunction "IO_L28P_5/D7_67") (pintype "bidirectional"))
    )
    (net (code "133") (name "/TXD4") (class "Default")
      (node (ref "U7") (pin "68") (pinfunction "IO_L28N_5/D6_68") (pintype "bidirectional"))
    )
    (net (code "134") (name "/TXD5") (class "Default")
      (node (ref "U7") (pin "71") (pinfunction "IO_71") (pintype "bidirectional"))
    )
    (net (code "135") (name "/TXD6") (class "Default")
      (node (ref "U7") (pin "72") (pinfunction "IO_L31P_5/D5_72") (pintype "bidirectional"))
    )
    (net (code "136") (name "/TXD7") (class "Default")
      (node (ref "U7") (pin "74") (pinfunction "IO_L31N_5/D4_74") (pintype "bidirectional"))
    )
    (net (code "138") (name "/TX_EN") (class "Default")
      (node (ref "U7") (pin "76") (pinfunction "IO_L32P_5/GCLK2_76") (pintype "bidirectional"))
    )
    (net (code "139") (name "/TX_ER") (class "Default")
      (node (ref "U7") (pin "78") (pinfunction "IO/VREF_5_78") (pintype "bidirectional"))
    )
    (net (code "140") (name "/~{OE}") (class "Default")
      (node (ref "U7") (pin "108") (pinfunction "IO_L17P_3/VREF_3_108") (pintype "bidirectional"))
    )
    (net (code "141") (name "/~{PROGRAM}") (class "Default")
      (node (ref "CONN1") (pin "54") (pinfunction "54_54") (pintype "passive"))
      (node (ref "R39") (pin "1") (pinfunction "1_1") (pintype "passive"))
      (node (ref "U7") (pin "207") (pinfunction "PROG_B_207") (pintype "input"))
    )
    (net (code "142") (name "/~{WE}") (class "Default")
      (node (ref "U7") (pin "107") (pinfunction "IO_L01N_3/VRP_3_107") (pintype "bidirectional"))
    )
    (net (code "143") (name "GND") (class "Default")
      (node (ref "CONN1") (pin "12") (pinfunction "12_12") (pintype "passive"))
      (node (ref "CONN1") (pin "17") (pinfunction "17_17") (pintype "passive"))
      (node (ref "CONN1") (pin "2") (pinfunction "2_2") (pintype "passive"))
      (node (ref "CONN1") (pin "22") (pinfunction "22_22") (pintype "passive"))
      (node (ref "CONN1") (pin "26") (pinfunction "26_26") (pintype "passive"))
      (node (ref "CONN1") (pin "29") (pinfunction "29_29") (pintype "passive"))
      (node (ref "CONN1") (pin "34") (pinfunction "34_34") (pintype "passive"))
      (node (ref "CONN1") (pin "39") (pinfunction "39_39") (pintype "passive"))
      (node (ref "CONN1") (pin "44") (pinfunction "44_44") (pintype "passive"))
      (node (ref "CONN1") (pin "49") (pinfunction "49_49") (pintype "passive"))
      (node (ref "CONN1") (pin "7") (pinfunction "7_7") (pintype "passive"))
      (node (ref "DS1") (pin "2") (pinfunction "K_2") (pintype "passive"))
      (node (ref "DS2") (pin "2") (pinfunction "K_2") (pintype "passive"))
      (node (ref "DS3") (pin "2") (pinfunction "K_2") (pintype "passive"))
      (node (ref "DS4") (pin "2") (pinfunction "K_2") (pintype "passive"))
      (node (ref "DS5") (pin "2") (pinfunction "K_2") (pintype "passive"))
      (node (ref "DS6") (pin "2") (pinfunction "K_2") (pintype "passive"))
      (node (ref "DS7") (pin "2") (pinfunction "K_2") (pintype "passive"))
      (node (ref "JP1") (pin "1") (pinfunction "1_1") (pintype "passive"))
      (node (ref "JP1") (pin "11") (pinfunction "11_11") (pintype "passive"))
      (node (ref "JP1") (pin "13") (pinfunction "13_13") (pintype "passive"))
      (node (ref "JP1") (pin "3") (pinfunction "3_3") (pintype "passive"))
      (node (ref "JP1") (pin "5") (pinfunction "5_5") (pintype "passive"))
      (node (ref "JP1") (pin "7") (pinfunction "7_7") (pintype "passive"))
      (node (ref "JP1") (pin "9") (pinfunction "9_9") (pintype "passive"))
      (node (ref "R25") (pin "1") (pinfunction "1_1") (pintype "passive"))
      (node (ref "R35") (pin "1") (pinfunction "1_1") (pintype "passive"))
      (node (ref "R45") (pin "2") (pinfunction "2_2") (pintype "passive"))
      (node (ref "R47") (pin "1") (pinfunction "1_1") (pintype "passive"))
      (node (ref "U7") (pin "1") (pinfunction "GND_1") (pintype "power_in"))
      (node (ref "U7") (pin "105") (pinfunction "GND_105") (pintype "power_in"))
      (node (ref "U7") (pin "112") (pinfunction "GND_112") (pintype "power_in"))
      (node (ref "U7") (pin "118") (pinfunction "GND_118") (pintype "power_in"))
      (node (ref "U7") (pin "129") (pinfunction "GND_129") (pintype "power_in"))
      (node (ref "U7") (pin "134") (pinfunction "GND_134") (pintype "power_in"))
      (node (ref "U7") (pin "14") (pinfunction "GND_14") (pintype "power_in"))
      (node (ref "U7") (pin "145") (pinfunction "GND_145") (pintype "power_in"))
      (node (ref "U7") (pin "151") (pinfunction "GND_151") (pintype "power_in"))
      (node (ref "U7") (pin "157") (pinfunction "GND_157") (pintype "power_in"))
      (node (ref "U7") (pin "163") (pinfunction "GND_163") (pintype "power_in"))
      (node (ref "U7") (pin "170") (pinfunction "GND_170") (pintype "power_in"))
      (node (ref "U7") (pin "179") (pinfunction "GND_179") (pintype "power_in"))
      (node (ref "U7") (pin "186") (pinfunction "GND_186") (pintype "power_in"))
      (node (ref "U7") (pin "195") (pinfunction "GND_195") (pintype "power_in"))
      (node (ref "U7") (pin "202") (pinfunction "GND_202") (pintype "power_in"))
      (node (ref "U7") (pin "25") (pinfunction "GND_25") (pintype "power_in"))
      (node (ref "U7") (pin "30") (pinfunction "GND_30") (pintype "power_in"))
      (node (ref "U7") (pin "41") (pinfunction "GND_41") (pintype "power_in"))
      (node (ref "U7") (pin "47") (pinfunction "GND_47") (pintype "power_in"))
      (node (ref "U7") (pin "53") (pinfunction "GND_53") (pintype "power_in"))
      (node (ref "U7") (pin "59") (pinfunction "GND_59") (pintype "power_in"))
      (node (ref "U7") (pin "66") (pinfunction "GND_66") (pintype "power_in"))
      (node (ref "U7") (pin "75") (pinfunction "GND_75") (pintype "power_in"))
      (node (ref "U7") (pin "8") (pinfunction "GND_8") (pintype "power_in"))
      (node (ref "U7") (pin "82") (pinfunction "GND_82") (pintype "power_in"))
      (node (ref "U7") (pin "91") (pinfunction "GND_91") (pintype "power_in"))
      (node (ref "U7") (pin "99") (pinfunction "GND_99") (pintype "power_in"))
    )
    (net (code "144") (name "Net-(DS1-A)") (class "Default")
      (node (ref "DS1") (pin "1") (pinfunction "A_1") (pintype "passive"))
      (node (ref "R2") (pin "1") (pintype "passive"))
    )
    (net (code "145") (name "Net-(DS2-A)") (class "Default")
      (node (ref "DS2") (pin "1") (pinfunction "A_1") (pintype "passive"))
      (node (ref "R3") (pin "1") (pintype "passive"))
    )
    (net (code "146") (name "Net-(DS3-A)") (class "Default")
      (node (ref "DS3") (pin "1") (pinfunction "A_1") (pintype "passive"))
      (node (ref "R4") (pin "1") (pintype "passive"))
    )
    (net (code "147") (name "Net-(DS4-A)") (class "Default")
      (node (ref "DS4") (pin "1") (pinfunction "A_1") (pintype "passive"))
      (node (ref "R5") (pin "1") (pintype "passive"))
    )
    (net (code "148") (name "Net-(DS5-A)") (class "Default")
      (node (ref "DS5") (pin "1") (pinfunction "A_1") (pintype "passive"))
      (node (ref "R6") (pin "1") (pintype "passive"))
    )
    (net (code "149") (name "Net-(DS6-A)") (class "Default")
      (node (ref "DS6") (pin "1") (pinfunction "A_1") (pintype "passive"))
      (node (ref "R7") (pin "1") (pintype "passive"))
    )
    (net (code "150") (name "Net-(DS7-A)") (class "Default")
      (node (ref "DS7") (pin "1") (pinfunction "A_1") (pintype "passive"))
      (node (ref "R1") (pin "1") (pintype "passive"))
    )
    (net (code "151") (name "Net-(U7A-IO_L01N_4{slash}VRP_4)") (class "Default")
      (node (ref "R25") (pin "2") (pinfunction "2_2") (pintype "passive"))
      (node (ref "U7") (pin "101") (pinfunction "IO_L01N_4/VRP_4_101") (pintype "bidirectional"))
    )
    (net (code "152") (name "Net-(U7A-IO_L01N_6{slash}VRP_6)") (class "Default")
      (node (ref "R47") (pin "2") (pinfunction "2_2") (pintype "passive"))
      (node (ref "U7") (pin "52") (pinfunction "IO_L01N_6/VRP_6_52") (pintype "bidirectional"))
    )
    (net (code "153") (name "Net-(U7A-IO_L01N_7{slash}VRP_7)") (class "Default")
      (node (ref "R45") (pin "1") (pinfunction "1_1") (pintype "passive"))
      (node (ref "U7") (pin "3") (pinfunction "IO_L01N_7/VRP_7_3") (pintype "bidirectional"))
    )
    (net (code "154") (name "Net-(U7A-IO_L01P_4{slash}VRN_4)") (class "Default")
      (node (ref "R26") (pin "1") (pinfunction "1_1") (pintype "passive"))
      (node (ref "U7") (pin "100") (pinfunction "IO_L01P_4/VRN_4_100") (pintype "bidirectional"))
    )
    (net (code "155") (name "Net-(U7A-IO_L01P_6{slash}VRN_6)") (class "Default")
      (node (ref "R46") (pin "1") (pinfunction "1_1") (pintype "passive"))
      (node (ref "U7") (pin "51") (pinfunction "IO_L01P_6/VRN_6_51") (pintype "bidirectional"))
    )
    (net (code "156") (name "Net-(U7A-IO_L01P_7{slash}VRN_7)") (class "Default")
      (node (ref "R38") (pin "1") (pinfunction "1_1") (pintype "passive"))
      (node (ref "U7") (pin "2") (pinfunction "IO_L01P_7/VRN_7_2") (pintype "bidirectional"))
    )
    (net (code "157") (name "Net-(U7A-IO_L10N_5{slash}VRP_5)") (class "Default")
      (node (ref "R35") (pin "2") (pinfunction "2_2") (pintype "passive"))
      (node (ref "U7") (pin "62") (pinfunction "IO_L10N_5/VRP_5_62") (pintype "bidirectional"))
    )
    (net (code "158") (name "Net-(U7A-IO_L10P_5{slash}VRN_5)") (class "Default")
      (node (ref "R36") (pin "1") (pinfunction "1_1") (pintype "passive"))
      (node (ref "U7") (pin "61") (pinfunction "IO_L10P_5/VRN_5_61") (pintype "bidirectional"))
    )
    (net (code "159") (name "Net-(U7A-IO_L27N_4{slash}DIN{slash}D0)") (class "Default")
      (node (ref "R40") (pin "1") (pintype "passive"))
      (node (ref "U7") (pin "92") (pinfunction "IO_L27N_4/DIN/D0_92") (pintype "bidirectional"))
    )
    (net (code "160") (name "Net-(U7B-CCLK)") (class "Default")
      (node (ref "R37") (pin "1") (pintype "passive"))
      (node (ref "U7") (pin "104") (pinfunction "CCLK_104") (pintype "input"))
    )
    (net (code "161") (name "Net-(U7B-TCK)") (class "Default")
      (node (ref "R41") (pin "1") (pintype "passive"))
      (node (ref "U7") (pin "159") (pinfunction "TCK_159") (pintype "bidirectional"))
    )
    (net (code "162") (name "Net-(U7B-TDI)") (class "Default")
      (node (ref "R42") (pin "1") (pintype "passive"))
      (node (ref "U7") (pin "208") (pinfunction "TDI_208") (pintype "bidirectional"))
    )
    (net (code "163") (name "Net-(U7B-TDO)") (class "Default")
      (node (ref "R43") (pin "1") (pintype "passive"))
      (node (ref "U7") (pin "158") (pinfunction "TDO_158") (pintype "bidirectional"))
    )
    (net (code "164") (name "Net-(U7B-TMS)") (class "Default")
      (node (ref "R44") (pin "1") (pintype "passive"))
      (node (ref "U7") (pin "160") (pinfunction "TMS_160") (pintype "bidirectional"))
    )
    (net (code "165") (name "VCC") (class "Default")
      (node (ref "CONN1") (pin "1") (pinfunction "1_1") (pintype "passive"))
      (node (ref "JP1") (pin "2") (pinfunction "2_2") (pintype "passive"))
      (node (ref "R26") (pin "2") (pinfunction "2_2") (pintype "passive"))
      (node (ref "R36") (pin "2") (pinfunction "2_2") (pintype "passive"))
      (node (ref "R38") (pin "2") (pinfunction "2_2") (pintype "passive"))
      (node (ref "R39") (pin "2") (pinfunction "2_2") (pintype "passive"))
      (node (ref "R46") (pin "2") (pinfunction "2_2") (pintype "passive"))
      (node (ref "U7") (pin "110") (pinfunction "VCCO_3_110") (pintype "power_in"))
      (node (ref "U7") (pin "127") (pinfunction "VCCO_3_127") (pintype "power_in"))
      (node (ref "U7") (pin "136") (pinfunction "VCCO_2_136") (pintype "power_in"))
      (node (ref "U7") (pin "153") (pinfunction "VCCO_2_153") (pintype "power_in"))
      (node (ref "U7") (pin "164") (pinfunction "VCCO_1_164") (pintype "power_in"))
      (node (ref "U7") (pin "177") (pinfunction "VCCO_1_177") (pintype "power_in"))
      (node (ref "U7") (pin "188") (pinfunction "VCCO_0_188") (pintype "power_in"))
      (node (ref "U7") (pin "201") (pinfunction "VCCO_0_201") (pintype "power_in"))
      (node (ref "U7") (pin "23") (pinfunction "VCCO_7_23") (pintype "power_in"))
      (node (ref "U7") (pin "32") (pinfunction "VCCO_6_32") (pintype "power_in"))
      (node (ref "U7") (pin "49") (pinfunction "VCCO_6_49") (pintype "power_in"))
      (node (ref "U7") (pin "54") (pinfunction "M1_54") (pintype "input"))
      (node (ref "U7") (pin "55") (pinfunction "M0_55") (pintype "input"))
      (node (ref "U7") (pin "56") (pinfunction "M2_56") (pintype "input"))
      (node (ref "U7") (pin "6") (pinfunction "VCCO_7_6") (pintype "power_in"))
      (node (ref "U7") (pin "60") (pinfunction "VCCO_5_60") (pintype "power_in"))
      (node (ref "U7") (pin "73") (pinfunction "VCCO_5_73") (pintype "power_in"))
      (node (ref "U7") (pin "84") (pinfunction "VCCO_4_84") (pintype "power_in"))
      (node (ref "U7") (pin "98") (pinfunction "VCCO_4_98") (pintype "power_in"))
    )
    (net (code "166") (name "unconnected-(JP1-Pad12)") (class "Default")
      (node (ref "JP1") (pin "12") (pinfunction "12_12") (pintype "passive+no_connect"))
    )
    (net (code "167") (name "unconnected-(JP1-Pad14)") (class "Default")
      (node (ref "JP1") (pin "14") (pinfunction "14_14") (pintype "passive+no_connect"))
    )
    (net (code "168") (name "unconnected-(U7A-IO_L01P_5{slash}CS_B-Pad57)") (class "Default")
      (node (ref "U7") (pin "57") (pinfunction "IO_L01P_5/CS_B_57") (pintype "bidirectional"))
    )
    (net (code "169") (name "unconnected-(U7A-IO_L31N_4{slash}INIT_B-Pad83)") (class "Default")
      (node (ref "U7") (pin "83") (pinfunction "IO_L31N_4/INIT_B_83") (pintype "bidirectional"))
    )
    (net (code "170") (name "unconnected-(U7A-IO_L32N_5{slash}GCLK3-Pad77)") (class "Default")
      (node (ref "U7") (pin "77") (pinfunction "IO_L32N_5/GCLK3_77") (pintype "bidirectional"))
    )
    (net (code "171") (name "unconnected-(U7A-IO_L40P_6{slash}VREF_6-Pad28)") (class "Default")
      (node (ref "U7") (pin "28") (pinfunction "IO_L40P_6/VREF_6_28") (pintype "bidirectional"))
    )
    (net (code "172") (name "unconnected-(U7B-DONE-Pad103)") (class "Default")
      (node (ref "U7") (pin "103") (pinfunction "DONE_103") (pintype "output"))
    )
    (net (code "173") (name "unconnected-(U7B-HSWAP_EN-Pad206)") (class "Default")
      (node (ref "U7") (pin "206") (pinfunction "HSWAP_EN_206") (pintype "input"))
    )
  )
)
